# Sensor.net
KiCad netlist of a schematic drawn in Altium Designer
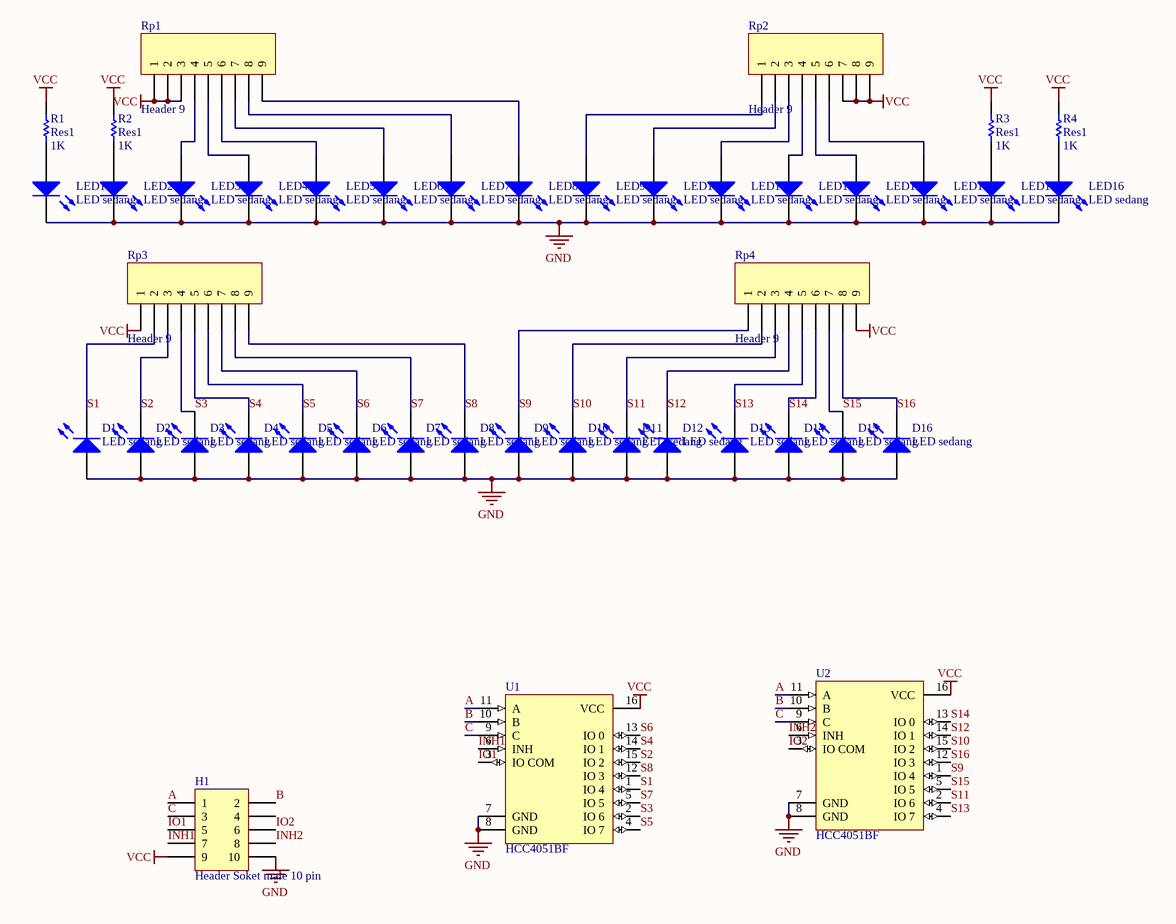
[diagram p0: Sensor.SchDoc]

(export (version "E")
  (design (tool "Eeschema 10.0.6"))
  (components
    (comp (ref "D1")
      (value "LED sedang")
      (footprint "LED sedang")
      (libsource (lib "agfa other components") (part "LED sedang"))
    )
    (comp (ref "D2")
      (value "LED sedang")
      (footprint "LED sedang")
      (libsource (lib "agfa other components") (part "LED sedang"))
    )
    (comp (ref "D3")
      (value "LED sedang")
      (footprint "LED sedang")
      (libsource (lib "agfa other components") (part "LED sedang"))
    )
    (comp (ref "D4")
      (value "LED sedang")
      (footprint "LED sedang")
      (libsource (lib "agfa other components") (part "LED sedang"))
    )
    (comp (ref "D5")
      (value "LED sedang")
      (footprint "LED sedang")
      (libsource (lib "agfa other components") (part "LED sedang"))
    )
    (comp (ref "D6")
      (value "LED sedang")
      (footprint "LED sedang")
      (libsource (lib "agfa other components") (part "LED sedang"))
    )
    (comp (ref "D7")
      (value "LED sedang")
      (footprint "LED sedang")
      (libsource (lib "agfa other components") (part "LED sedang"))
    )
    (comp (ref "D8")
      (value "LED sedang")
      (footprint "LED sedang")
      (libsource (lib "agfa other components") (part "LED sedang"))
    )
    (comp (ref "D9")
      (value "LED sedang")
      (footprint "LED sedang")
      (libsource (lib "agfa other components") (part "LED sedang"))
    )
    (comp (ref "D10")
      (value "LED sedang")
      (footprint "LED sedang")
      (libsource (lib "agfa other components") (part "LED sedang"))
    )
    (comp (ref "D11")
      (value "LED sedang")
      (footprint "LED sedang")
      (libsource (lib "agfa other components") (part "LED sedang"))
    )
    (comp (ref "D12")
      (value "LED sedang")
      (footprint "LED sedang")
      (libsource (lib "agfa other components") (part "LED sedang"))
    )
    (comp (ref "D13")
      (value "LED sedang")
      (footprint "LED sedang")
      (libsource (lib "agfa other components") (part "LED sedang"))
    )
    (comp (ref "D14")
      (value "LED sedang")
      (footprint "LED sedang")
      (libsource (lib "agfa other components") (part "LED sedang"))
    )
    (comp (ref "D15")
      (value "LED sedang")
      (footprint "LED sedang")
      (libsource (lib "agfa other components") (part "LED sedang"))
    )
    (comp (ref "D16")
      (value "LED sedang")
      (footprint "LED sedang")
      (libsource (lib "agfa other components") (part "LED sedang"))
    )
    (comp (ref "H1")
      (value "Header Soket male 10 pin")
      (footprint "Header Soket male 10 pin")
      (libsource (lib "agfa other components") (part "Header Soket male 10 pin"))
    )
    (comp (ref "LED1")
      (value "LED sedang")
      (footprint "LED sedang")
      (libsource (lib "agfa other components") (part "LED sedang"))
    )
    (comp (ref "LED2")
      (value "LED sedang")
      (footprint "LED sedang")
      (libsource (lib "agfa other components") (part "LED sedang"))
    )
    (comp (ref "LED3")
      (value "LED sedang")
      (footprint "LED sedang")
      (libsource (lib "agfa other components") (part "LED sedang"))
    )
    (comp (ref "LED4")
      (value "LED sedang")
      (footprint "LED sedang")
      (libsource (lib "agfa other components") (part "LED sedang"))
    )
    (comp (ref "LED5")
      (value "LED sedang")
      (footprint "LED sedang")
      (libsource (lib "agfa other components") (part "LED sedang"))
    )
    (comp (ref "LED6")
      (value "LED sedang")
      (footprint "LED sedang")
      (libsource (lib "agfa other components") (part "LED sedang"))
    )
    (comp (ref "LED7")
      (value "LED sedang")
      (footprint "LED sedang")
      (libsource (lib "agfa other components") (part "LED sedang"))
    )
    (comp (ref "LED8")
      (value "LED sedang")
      (footprint "LED sedang")
      (libsource (lib "agfa other components") (part "LED sedang"))
    )
    (comp (ref "LED9")
      (value "LED sedang")
      (footprint "LED sedang")
      (libsource (lib "agfa other components") (part "LED sedang"))
    )
    (comp (ref "LED10")
      (value "LED sedang")
      (footprint "LED sedang")
      (libsource (lib "agfa other components") (part "LED sedang"))
    )
    (comp (ref "LED11")
      (value "LED sedang")
      (footprint "LED sedang")
      (libsource (lib "agfa other components") (part "LED sedang"))
    )
    (comp (ref "LED12")
      (value "LED sedang")
      (footprint "LED sedang")
      (libsource (lib "agfa other components") (part "LED sedang"))
    )
    (comp (ref "LED13")
      (value "LED sedang")
      (footprint "LED sedang")
      (libsource (lib "agfa other components") (part "LED sedang"))
    )
    (comp (ref "LED14")
      (value "LED sedang")
      (footprint "LED sedang")
      (libsource (lib "agfa other components") (part "LED sedang"))
    )
    (comp (ref "LED15")
      (value "LED sedang")
      (footprint "LED sedang")
      (libsource (lib "agfa other components") (part "LED sedang"))
    )
    (comp (ref "LED16")
      (value "LED sedang")
      (footprint "LED sedang")
      (libsource (lib "agfa other components") (part "LED sedang"))
    )
    (comp (ref "R1")
      (value "Res1")
      (footprint "AXIAL-0.3")
      (description "Resistor")
      (fields (field (name "ALTIUM_VALUE") "1K") (field (name "PUBLISHER") "Altium Limited"))
      (libsource (lib "Miscellaneous Devices") (part "Res1"))
    )
    (comp (ref "R2")
      (value "Res1")
      (footprint "AXIAL-0.3")
      (description "Resistor")
      (fields (field (name "ALTIUM_VALUE") "1K") (field (name "PUBLISHER") "Altium Limited"))
      (libsource (lib "Miscellaneous Devices") (part "Res1"))
    )
    (comp (ref "R3")
      (value "Res1")
      (footprint "AXIAL-0.3")
      (description "Resistor")
      (fields (field (name "ALTIUM_VALUE") "1K") (field (name "PUBLISHER") "Altium Limited"))
      (libsource (lib "Miscellaneous Devices") (part "Res1"))
    )
    (comp (ref "R4")
      (value "Res1")
      (footprint "AXIAL-0.3")
      (description "Resistor")
      (fields (field (name "ALTIUM_VALUE") "1K") (field (name "PUBLISHER") "Altium Limited"))
      (libsource (lib "Miscellaneous Devices") (part "Res1"))
    )
    (comp (ref "Rp1")
      (value "Header 9")
      (footprint "HDR1X9")
      (description "Header, 9-Pin")
      (fields (field (name "PUBLISHER") "Altium Limited"))
      (libsource (lib "Miscellaneous Connectors") (part "Header 9"))
    )
    (comp (ref "Rp2")
      (value "Header 9")
      (footprint "HDR1X9")
      (description "Header, 9-Pin")
      (fields (field (name "PUBLISHER") "Altium Limited"))
      (libsource (lib "Miscellaneous Connectors") (part "Header 9"))
    )
    (comp (ref "Rp3")
      (value "Header 9")
      (footprint "HDR1X9")
      (description "Header, 9-Pin")
      (fields (field (name "PUBLISHER") "Altium Limited"))
      (libsource (lib "Miscellaneous Connectors") (part "Header 9"))
    )
    (comp (ref "Rp4")
      (value "Header 9")
      (footprint "HDR1X9")
      (description "Header, 9-Pin")
      (fields (field (name "PUBLISHER") "Altium Limited"))
      (libsource (lib "Miscellaneous Connectors") (part "Header 9"))
    )
    (comp (ref "U1")
      (value "HCC4051BF")
      (footprint "DIP16")
      (description "Analog Multiplexer/Demultiplexer")
      (fields (field (name "PUBLISHER") "Altium Limited"))
      (libsource (lib "ST Logic Multiplexer") (part "HCC4051BF"))
    )
    (comp (ref "U2")
      (value "HCC4051BF")
      (footprint "DIP16")
      (description "Analog Multiplexer/Demultiplexer")
      (fields (field (name "PUBLISHER") "Altium Limited"))
      (libsource (lib "ST Logic Multiplexer") (part "HCC4051BF"))
    )
  )
  (nets
    (net (code "1") (name "/A") (class "Default")
      (node (ref "H1") (pin "1") (pinfunction "1_1") (pintype "passive"))
      (node (ref "U1") (pin "11") (pinfunction "A_11") (pintype "input"))
      (node (ref "U2") (pin "11") (pinfunction "A_11") (pintype "input"))
    )
    (net (code "2") (name "/B") (class "Default")
      (node (ref "H1") (pin "2") (pinfunction "2_2") (pintype "passive"))
      (node (ref "U1") (pin "10") (pinfunction "B_10") (pintype "input"))
      (node (ref "U2") (pin "10") (pinfunction "B_10") (pintype "input"))
    )
    (net (code "3") (name "/C") (class "Default")
      (node (ref "H1") (pin "3") (pinfunction "3_3") (pintype "passive"))
      (node (ref "U1") (pin "9") (pinfunction "C_9") (pintype "input"))
      (node (ref "U2") (pin "9") (pinfunction "C_9") (pintype "input"))
    )
    (net (code "4") (name "/INH1") (class "Default")
      (node (ref "H1") (pin "7") (pinfunction "7_7") (pintype "passive"))
      (node (ref "U1") (pin "6") (pinfunction "INH_6") (pintype "input"))
    )
    (net (code "5") (name "/INH2") (class "Default")
      (node (ref "H1") (pin "8") (pinfunction "8_8") (pintype "passive"))
      (node (ref "U2") (pin "6") (pinfunction "INH_6") (pintype "input"))
    )
    (net (code "6") (name "/IO1") (class "Default")
      (node (ref "H1") (pin "5") (pinfunction "5_5") (pintype "passive"))
      (node (ref "U1") (pin "3") (pinfunction "IO_COM_3") (pintype "bidirectional"))
    )
    (net (code "7") (name "/IO2") (class "Default")
      (node (ref "H1") (pin "6") (pinfunction "6_6") (pintype "passive"))
      (node (ref "U2") (pin "3") (pinfunction "IO_COM_3") (pintype "bidirectional"))
    )
    (net (code "8") (name "/S1") (class "Default")
      (node (ref "D1") (pin "2") (pinfunction "K_2") (pintype "passive"))
      (node (ref "Rp3") (pin "2") (pinfunction "2_2") (pintype "passive"))
      (node (ref "U1") (pin "1") (pinfunction "IO_4_1") (pintype "bidirectional"))
    )
    (net (code "9") (name "/S2") (class "Default")
      (node (ref "D2") (pin "2") (pinfunction "K_2") (pintype "passive"))
      (node (ref "Rp3") (pin "3") (pinfunction "3_3") (pintype "passive"))
      (node (ref "U1") (pin "15") (pinfunction "IO_2_15") (pintype "bidirectional"))
    )
    (net (code "10") (name "/S3") (class "Default")
      (node (ref "D3") (pin "2") (pinfunction "K_2") (pintype "passive"))
      (node (ref "Rp3") (pin "4") (pinfunction "4_4") (pintype "passive"))
      (node (ref "U1") (pin "2") (pinfunction "IO_6_2") (pintype "bidirectional"))
    )
    (net (code "11") (name "/S4") (class "Default")
      (node (ref "D4") (pin "2") (pinfunction "K_2") (pintype "passive"))
      (node (ref "Rp3") (pin "5") (pinfunction "5_5") (pintype "passive"))
      (node (ref "U1") (pin "14") (pinfunction "IO_1_14") (pintype "bidirectional"))
    )
    (net (code "12") (name "/S5") (class "Default")
      (node (ref "D5") (pin "2") (pinfunction "K_2") (pintype "passive"))
      (node (ref "Rp3") (pin "6") (pinfunction "6_6") (pintype "passive"))
      (node (ref "U1") (pin "4") (pinfunction "IO_7_4") (pintype "bidirectional"))
    )
    (net (code "13") (name "/S6") (class "Default")
      (node (ref "D6") (pin "2") (pinfunction "K_2") (pintype "passive"))
      (node (ref "Rp3") (pin "7") (pinfunction "7_7") (pintype "passive"))
      (node (ref "U1") (pin "13") (pinfunction "IO_0_13") (pintype "bidirectional"))
    )
    (net (code "14") (name "/S7") (class "Default")
      (node (ref "D7") (pin "2") (pinfunction "K_2") (pintype "passive"))
      (node (ref "Rp3") (pin "8") (pinfunction "8_8") (pintype "passive"))
      (node (ref "U1") (pin "5") (pinfunction "IO_5_5") (pintype "bidirectional"))
    )
    (net (code "15") (name "/S8") (class "Default")
      (node (ref "D8") (pin "2") (pinfunction "K_2") (pintype "passive"))
      (node (ref "Rp3") (pin "9") (pinfunction "9_9") (pintype "passive"))
      (node (ref "U1") (pin "12") (pinfunction "IO_3_12") (pintype "bidirectional"))
    )
    (net (code "16") (name "/S9") (class "Default")
      (node (ref "D9") (pin "2") (pinfunction "K_2") (pintype "passive"))
      (node (ref "Rp4") (pin "1") (pinfunction "1_1") (pintype "passive"))
      (node (ref "U2") (pin "1") (pinfunction "IO_4_1") (pintype "bidirectional"))
    )
    (net (code "17") (name "/S10") (class "Default")
      (node (ref "D10") (pin "2") (pinfunction "K_2") (pintype "passive"))
      (node (ref "Rp4") (pin "2") (pinfunction "2_2") (pintype "passive"))
      (node (ref "U2") (pin "15") (pinfunction "IO_2_15") (pintype "bidirectional"))
    )
    (net (code "18") (name "/S11") (class "Default")
      (node (ref "D11") (pin "2") (pinfunction "K_2") (pintype "passive"))
      (node (ref "Rp4") (pin "3") (pinfunction "3_3") (pintype "passive"))
      (node (ref "U2") (pin "2") (pinfunction "IO_6_2") (pintype "bidirectional"))
    )
    (net (code "19") (name "/S12") (class "Default")
      (node (ref "D12") (pin "2") (pinfunction "K_2") (pintype "passive"))
      (node (ref "Rp4") (pin "4") (pinfunction "4_4") (pintype "passive"))
      (node (ref "U2") (pin "14") (pinfunction "IO_1_14") (pintype "bidirectional"))
    )
    (net (code "20") (name "/S13") (class "Default")
      (node (ref "D13") (pin "2") (pinfunction "K_2") (pintype "passive"))
      (node (ref "Rp4") (pin "5") (pinfunction "5_5") (pintype "passive"))
      (node (ref "U2") (pin "4") (pinfunction "IO_7_4") (pintype "bidirectional"))
    )
    (net (code "21") (name "/S14") (class "Default")
      (node (ref "D14") (pin "2") (pinfunction "K_2") (pintype "passive"))
      (node (ref "Rp4") (pin "6") (pinfunction "6_6") (pintype "passive"))
      (node (ref "U2") (pin "13") (pinfunction "IO_0_13") (pintype "bidirectional"))
    )
    (net (code "22") (name "/S15") (class "Default")
      (node (ref "D15") (pin "2") (pinfunction "K_2") (pintype "passive"))
      (node (ref "Rp4") (pin "7") (pinfunction "7_7") (pintype "passive"))
      (node (ref "U2") (pin "5") (pinfunction "IO_5_5") (pintype "bidirectional"))
    )
    (net (code "23") (name "/S16") (class "Default")
      (node (ref "D16") (pin "2") (pinfunction "K_2") (pintype "passive"))
      (node (ref "Rp4") (pin "8") (pinfunction "8_8") (pintype "passive"))
      (node (ref "U2") (pin "12") (pinfunction "IO_3_12") (pintype "bidirectional"))
    )
    (net (code "24") (name "GND") (class "Default")
      (node (ref "D1") (pin "1") (pinfunction "A_1") (pintype "passive"))
      (node (ref "D10") (pin "1") (pinfunction "A_1") (pintype "passive"))
      (node (ref "D11") (pin "1") (pinfunction "A_1") (pintype "passive"))
      (node (ref "D12") (pin "1") (pinfunction "A_1") (pintype "passive"))
      (node (ref "D13") (pin "1") (pinfunction "A_1") (pintype "passive"))
      (node (ref "D14") (pin "1") (pinfunction "A_1") (pintype "passive"))
      (node (ref "D15") (pin "1") (pinfunction "A_1") (pintype "passive"))
      (node (ref "D16") (pin "1") (pinfunction "A_1") (pintype "passive"))
      (node (ref "D2") (pin "1") (pinfunction "A_1") (pintype "passive"))
      (node (ref "D3") (pin "1") (pinfunction "A_1") (pintype "passive"))
      (node (ref "D4") (pin "1") (pinfunction "A_1") (pintype "passive"))
      (node (ref "D5") (pin "1") (pinfunction "A_1") (pintype "passive"))
      (node (ref "D6") (pin "1") (pinfunction "A_1") (pintype "passive"))
      (node (ref "D7") (pin "1") (pinfunction "A_1") (pintype "passive"))
      (node (ref "D8") (pin "1") (pinfunction "A_1") (pintype "passive"))
      (node (ref "D9") (pin "1") (pinfunction "A_1") (pintype "passive"))
      (node (ref "H1") (pin "10") (pinfunction "10_10") (pintype "passive"))
      (node (ref "LED1") (pin "2") (pinfunction "K_2") (pintype "passive"))
      (node (ref "LED10") (pin "2") (pinfunction "K_2") (pintype "passive"))
      (node (ref "LED11") (pin "2") (pinfunction "K_2") (pintype "passive"))
      (node (ref "LED12") (pin "2") (pinfunction "K_2") (pintype "passive"))
      (node (ref "LED13") (pin "2") (pinfunction "K_2") (pintype "passive"))
      (node (ref "LED14") (pin "2") (pinfunction "K_2") (pintype "passive"))
      (node (ref "LED15") (pin "2") (pinfunction "K_2") (pintype "passive"))
      (node (ref "LED16") (pin "2") (pinfunction "K_2") (pintype "passive"))
      (node (ref "LED2") (pin "2") (pinfunction "K_2") (pintype "passive"))
      (node (ref "LED3") (pin "2") (pinfunction "K_2") (pintype "passive"))
      (node (ref "LED4") (pin "2") (pinfunction "K_2") (pintype "passive"))
      (node (ref "LED5") (pin "2") (pinfunction "K_2") (pintype "passive"))
      (node (ref "LED6") (pin "2") (pinfunction "K_2") (pintype "passive"))
      (node (ref "LED7") (pin "2") (pinfunction "K_2") (pintype "passive"))
      (node (ref "LED8") (pin "2") (pinfunction "K_2") (pintype "passive"))
      (node (ref "LED9") (pin "2") (pinfunction "K_2") (pintype "passive"))
      (node (ref "U1") (pin "7") (pinfunction "GND_7") (pintype "power_in"))
      (node (ref "U1") (pin "8") (pinfunction "GND_8") (pintype "power_in"))
      (node (ref "U2") (pin "7") (pinfunction "GND_7") (pintype "power_in"))
      (node (ref "U2") (pin "8") (pinfunction "GND_8") (pintype "power_in"))
    )
    (net (code "25") (name "Net-(LED1-A)") (class "Default")
      (node (ref "LED1") (pin "1") (pinfunction "A_1") (pintype "passive"))
      (node (ref "R1") (pin "1") (pinfunction "1_1") (pintype "passive"))
    )
    (net (code "26") (name "Net-(LED2-A)") (class "Default")
      (node (ref "LED2") (pin "1") (pinfunction "A_1") (pintype "passive"))
      (node (ref "R2") (pin "1") (pinfunction "1_1") (pintype "passive"))
    )
    (net (code "27") (name "Net-(LED3-A)") (class "Default")
      (node (ref "LED3") (pin "1") (pinfunction "A_1") (pintype "passive"))
      (node (ref "Rp1") (pin "4") (pinfunction "4_4") (pintype "passive"))
    )
    (net (code "28") (name "Net-(LED4-A)") (class "Default")
      (node (ref "LED4") (pin "1") (pinfunction "A_1") (pintype "passive"))
      (node (ref "Rp1") (pin "5") (pinfunction "5_5") (pintype "passive"))
    )
    (net (code "29") (name "Net-(LED5-A)") (class "Default")
      (node (ref "LED5") (pin "1") (pinfunction "A_1") (pintype "passive"))
      (node (ref "Rp1") (pin "6") (pinfunction "6_6") (pintype "passive"))
    )
    (net (code "30") (name "Net-(LED6-A)") (class "Default")
      (node (ref "LED6") (pin "1") (pinfunction "A_1") (pintype "passive"))
      (node (ref "Rp1") (pin "7") (pinfunction "7_7") (pintype "passive"))
    )
    (net (code "31") (name "Net-(LED7-A)") (class "Default")
      (node (ref "LED7") (pin "1") (pinfunction "A_1") (pintype "passive"))
      (node (ref "Rp1") (pin "8") (pinfunction "8_8") (pintype "passive"))
    )
    (net (code "32") (name "Net-(LED8-A)") (class "Default")
      (node (ref "LED8") (pin "1") (pinfunction "A_1") (pintype "passive"))
      (node (ref "Rp1") (pin "9") (pinfunction "9_9") (pintype "passive"))
    )
    (net (code "33") (name "Net-(LED9-A)") (class "Default")
      (node (ref "LED9") (pin "1") (pinfunction "A_1") (pintype "passive"))
      (node (ref "Rp2") (pin "1") (pinfunction "1_1") (pintype "passive"))
    )
    (net (code "34") (name "Net-(LED10-A)") (class "Default")
      (node (ref "LED10") (pin "1") (pinfunction "A_1") (pintype "passive"))
      (node (ref "Rp2") (pin "2") (pinfunction "2_2") (pintype "passive"))
    )
    (net (code "35") (name "Net-(LED11-A)") (class "Default")
      (node (ref "LED11") (pin "1") (pinfunction "A_1") (pintype "passive"))
      (node (ref "Rp2") (pin "3") (pinfunction "3_3") (pintype "passive"))
    )
    (net (code "36") (name "Net-(LED12-A)") (class "Default")
      (node (ref "LED12") (pin "1") (pinfunction "A_1") (pintype "passive"))
      (node (ref "Rp2") (pin "4") (pinfunction "4_4") (pintype "passive"))
    )
    (net (code "37") (name "Net-(LED13-A)") (class "Default")
      (node (ref "LED13") (pin "1") (pinfunction "A_1") (pintype "passive"))
      (node (ref "Rp2") (pin "5") (pinfunction "5_5") (pintype "passive"))
    )
    (net (code "38") (name "Net-(LED14-A)") (class "Default")
      (node (ref "LED14") (pin "1") (pinfunction "A_1") (pintype "passive"))
      (node (ref "Rp2") (pin "6") (pinfunction "6_6") (pintype "passive"))
    )
    (net (code "39") (name "Net-(LED15-A)") (class "Default")
      (node (ref "LED15") (pin "1") (pinfunction "A_1") (pintype "passive"))
      (node (ref "R3") (pin "1") (pinfunction "1_1") (pintype "passive"))
    )
    (net (code "40") (name "Net-(LED16-A)") (class "Default")
      (node (ref "LED16") (pin "1") (pinfunction "A_1") (pintype "passive"))
      (node (ref "R4") (pin "1") (pinfunction "1_1") (pintype "passive"))
    )
    (net (code "41") (name "VCC") (class "Default")
      (node (ref "H1") (pin "9") (pinfunction "9_9") (pintype "passive"))
      (node (ref "R1") (pin "2") (pinfunction "2_2") (pintype "passive"))
      (node (ref "R2") (pin "2") (pinfunction "2_2") (pintype "passive"))
      (node (ref "R3") (pin "2") (pinfunction "2_2") (pintype "passive"))
      (node (ref "R4") (pin "2") (pinfunction "2_2") (pintype "passive"))
      (node (ref "Rp1") (pin "1") (pinfunction "1_1") (pintype "passive"))
      (node (ref "Rp1") (pin "2") (pinfunction "2_2") (pintype "passive"))
      (node (ref "Rp1") (pin "3") (pinfunction "3_3") (pintype "passive"))
      (node (ref "Rp2") (pin "7") (pinfunction "7_7") (pintype "passive"))
      (node (ref "Rp2") (pin "8") (pinfunction "8_8") (pintype "passive"))
      (node (ref "Rp2") (pin "9") (pinfunction "9_9") (pintype "passive"))
      (node (ref "Rp3") (pin "1") (pinfunction "1_1") (pintype "passive"))
      (node (ref "Rp4") (pin "9") (pinfunction "9_9") (pintype "passive"))
      (node (ref "U1") (pin "16") (pinfunction "VCC_16") (pintype "power_in"))
      (node (ref "U2") (pin "16") (pinfunction "VCC_16") (pintype "power_in"))
    )
    (net (code "42") (name "unconnected-(H1-Pad4)") (class "Default")
      (node (ref "H1") (pin "4") (pinfunction "4_4") (pintype "passive"))
    )
  )
)
